# FilterControl_Schematic.net
KiCad netlist of a schematic drawn in Altium Designer
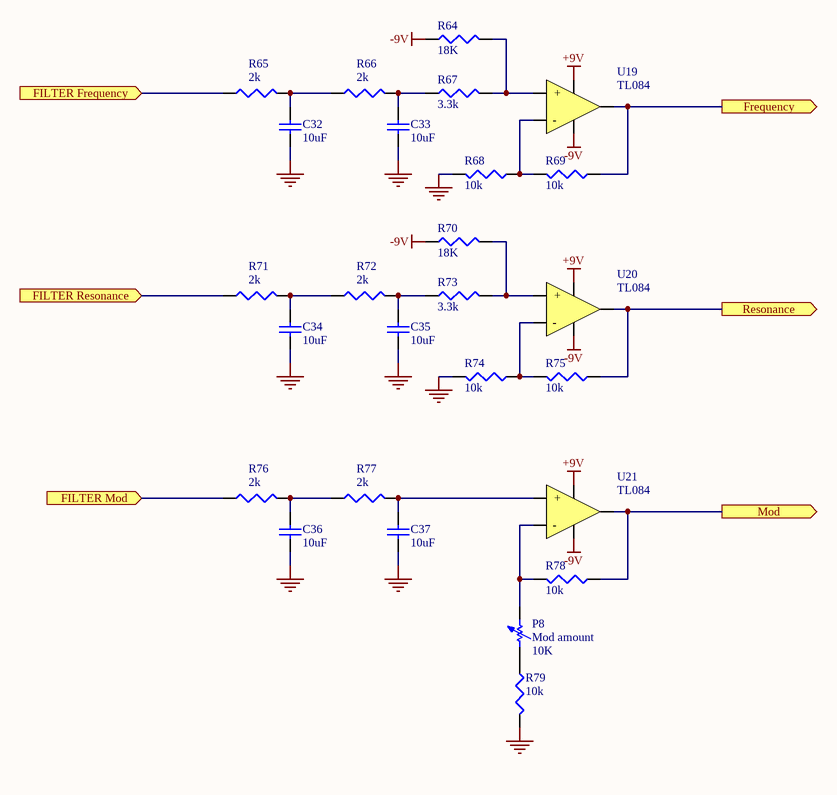
[diagram p0: FilterControl.Schematic.SchDoc]

(export (version "E")
  (design (tool "Eeschema 10.0.6"))
  (components
    (comp (ref "C32")
      (value "10uF")
      (footprint "CAPC1608N")
      (description "Capacitor (Semiconductor SIM Model)")
      (fields (field (name "PUBLISHER") "Altium Limited"))
      (libsource (lib "Miscellaneous Devices") (part "Cap Semi"))
    )
    (comp (ref "C33")
      (value "10uF")
      (footprint "CAPC1608N")
      (description "Capacitor (Semiconductor SIM Model)")
      (fields (field (name "PUBLISHER") "Altium Limited"))
      (libsource (lib "Miscellaneous Devices") (part "Cap Semi"))
    )
    (comp (ref "C34")
      (value "10uF")
      (footprint "CAPC1608N")
      (description "Capacitor (Semiconductor SIM Model)")
      (fields (field (name "PUBLISHER") "Altium Limited"))
      (libsource (lib "Miscellaneous Devices") (part "Cap Semi"))
    )
    (comp (ref "C35")
      (value "10uF")
      (footprint "CAPC1608N")
      (description "Capacitor (Semiconductor SIM Model)")
      (fields (field (name "PUBLISHER") "Altium Limited"))
      (libsource (lib "Miscellaneous Devices") (part "Cap Semi"))
    )
    (comp (ref "C36")
      (value "10uF")
      (footprint "CAPC1608N")
      (description "Capacitor (Semiconductor SIM Model)")
      (fields (field (name "PUBLISHER") "Altium Limited"))
      (libsource (lib "Miscellaneous Devices") (part "Cap Semi"))
    )
    (comp (ref "C37")
      (value "10uF")
      (footprint "CAPC1608N")
      (description "Capacitor (Semiconductor SIM Model)")
      (fields (field (name "PUBLISHER") "Altium Limited"))
      (libsource (lib "Miscellaneous Devices") (part "Cap Semi"))
    )
    (comp (ref "P8")
      (value "Mod amount")
      (footprint "AXIAL-0.7")
      (description "Variable Resistor")
      (fields (field (name "ALTIUM_VALUE") "10K") (field (name "PUBLISHER") "Altium Limited"))
      (libsource (lib "Miscellaneous Devices") (part "Res Adj1"))
    )
    (comp (ref "R64")
      (value "18K")
      (footprint "CAPC1608N")
      (description "Resistor")
      (fields (field (name "PUBLISHER") "Altium Limited"))
      (libsource (lib "Miscellaneous Devices") (part "Res3"))
    )
    (comp (ref "R65")
      (value "2k")
      (footprint "CAPC1608N")
      (description "Resistor")
      (fields (field (name "PUBLISHER") "Altium Limited"))
      (libsource (lib "Miscellaneous Devices") (part "Res3"))
    )
    (comp (ref "R66")
      (value "2k")
      (footprint "CAPC1608N")
      (description "Resistor")
      (fields (field (name "PUBLISHER") "Altium Limited"))
      (libsource (lib "Miscellaneous Devices") (part "Res3"))
    )
    (comp (ref "R67")
      (value "3.3k")
      (footprint "CAPC1608N")
      (description "Resistor")
      (fields (field (name "PUBLISHER") "Altium Limited"))
      (libsource (lib "Miscellaneous Devices") (part "Res3"))
    )
    (comp (ref "R68")
      (value "10k")
      (footprint "CAPC1608N")
      (description "Resistor")
      (fields (field (name "PUBLISHER") "Altium Limited"))
      (libsource (lib "Miscellaneous Devices") (part "Res3"))
    )
    (comp (ref "R69")
      (value "10k")
      (footprint "CAPC1608N")
      (description "Resistor")
      (fields (field (name "PUBLISHER") "Altium Limited"))
      (libsource (lib "Miscellaneous Devices") (part "Res3"))
    )
    (comp (ref "R70")
      (value "18K")
      (footprint "CAPC1608N")
      (description "Resistor")
      (fields (field (name "PUBLISHER") "Altium Limited"))
      (libsource (lib "Miscellaneous Devices") (part "Res3"))
    )
    (comp (ref "R71")
      (value "2k")
      (footprint "CAPC1608N")
      (description "Resistor")
      (fields (field (name "PUBLISHER") "Altium Limited"))
      (libsource (lib "Miscellaneous Devices") (part "Res3"))
    )
    (comp (ref "R72")
      (value "2k")
      (footprint "CAPC1608N")
      (description "Resistor")
      (fields (field (name "PUBLISHER") "Altium Limited"))
      (libsource (lib "Miscellaneous Devices") (part "Res3"))
    )
    (comp (ref "R73")
      (value "3.3k")
      (footprint "CAPC1608N")
      (description "Resistor")
      (fields (field (name "PUBLISHER") "Altium Limited"))
      (libsource (lib "Miscellaneous Devices") (part "Res3"))
    )
    (comp (ref "R74")
      (value "10k")
      (footprint "CAPC1608N")
      (description "Resistor")
      (fields (field (name "PUBLISHER") "Altium Limited"))
      (libsource (lib "Miscellaneous Devices") (part "Res3"))
    )
    (comp (ref "R75")
      (value "10k")
      (footprint "CAPC1608N")
      (description "Resistor")
      (fields (field (name "PUBLISHER") "Altium Limited"))
      (libsource (lib "Miscellaneous Devices") (part "Res3"))
    )
    (comp (ref "R76")
      (value "2k")
      (footprint "CAPC1608N")
      (description "Resistor")
      (fields (field (name "PUBLISHER") "Altium Limited"))
      (libsource (lib "Miscellaneous Devices") (part "Res3"))
    )
    (comp (ref "R77")
      (value "2k")
      (footprint "CAPC1608N")
      (description "Resistor")
      (fields (field (name "PUBLISHER") "Altium Limited"))
      (libsource (lib "Miscellaneous Devices") (part "Res3"))
    )
    (comp (ref "R78")
      (value "10k")
      (footprint "CAPC1608N")
      (description "Resistor")
      (fields (field (name "PUBLISHER") "Altium Limited"))
      (libsource (lib "Miscellaneous Devices") (part "Res3"))
    )
    (comp (ref "R79")
      (value "10k")
      (footprint "CAPC1608N")
      (description "Resistor")
      (fields (field (name "PUBLISHER") "Altium Limited"))
      (libsource (lib "Miscellaneous Devices") (part "Res3"))
    )
    (comp (ref "U19")
      (value "TL084")
      (footprint "TL084")
      (libsource (lib "SynthyTwo.Components") (part "TL084"))
    )
    (comp (ref "U20")
      (value "TL084")
      (footprint "TL084")
      (libsource (lib "SynthyTwo.Components") (part "TL084"))
    )
    (comp (ref "U21")
      (value "TL084")
      (footprint "TL084")
      (libsource (lib "SynthyTwo.Components") (part "TL084"))
    )
  )
  (nets
    (net (code "1") (name "+9V") (class "Default")
      (node (ref "U19") (pin "4") (pinfunction "VCC+_4") (pintype "passive"))
      (node (ref "U20") (pin "4") (pinfunction "VCC+_4") (pintype "passive"))
      (node (ref "U21") (pin "4") (pinfunction "VCC+_4") (pintype "passive"))
    )
    (net (code "2") (name "-9V") (class "Default")
      (node (ref "R64") (pin "1") (pinfunction "1_1") (pintype "passive"))
      (node (ref "R70") (pin "1") (pinfunction "1_1") (pintype "passive"))
      (node (ref "U19") (pin "11") (pinfunction "VCC-_11") (pintype "passive"))
      (node (ref "U20") (pin "11") (pinfunction "VCC-_11") (pintype "passive"))
      (node (ref "U21") (pin "11") (pinfunction "VCC-_11") (pintype "passive"))
    )
    (net (code "3") (name "/FILTER Frequency") (class "Default")
      (node (ref "R65") (pin "1") (pinfunction "1_1") (pintype "passive"))
    )
    (net (code "4") (name "/FILTER Mod") (class "Default")
      (node (ref "R76") (pin "1") (pinfunction "1_1") (pintype "passive"))
    )
    (net (code "5") (name "/FILTER Resonance") (class "Default")
      (node (ref "R71") (pin "1") (pinfunction "1_1") (pintype "passive"))
    )
    (net (code "6") (name "/Frequency") (class "Default")
      (node (ref "R69") (pin "1") (pinfunction "1_1") (pintype "passive"))
      (node (ref "U19") (pin "1") (pinfunction "OUT_1") (pintype "passive"))
    )
    (net (code "7") (name "/Mod") (class "Default")
      (node (ref "R78") (pin "1") (pinfunction "1_1") (pintype "passive"))
      (node (ref "U21") (pin "1") (pinfunction "OUT_1") (pintype "passive"))
    )
    (net (code "8") (name "/Resonance") (class "Default")
      (node (ref "R75") (pin "1") (pinfunction "1_1") (pintype "passive"))
      (node (ref "U20") (pin "1") (pinfunction "OUT_1") (pintype "passive"))
    )
    (net (code "9") (name "GND") (class "Default")
      (node (ref "C32") (pin "1") (pinfunction "1_1") (pintype "passive"))
      (node (ref "C33") (pin "1") (pinfunction "1_1") (pintype "passive"))
      (node (ref "C34") (pin "1") (pinfunction "1_1") (pintype "passive"))
      (node (ref "C35") (pin "1") (pinfunction "1_1") (pintype "passive"))
      (node (ref "C36") (pin "1") (pinfunction "1_1") (pintype "passive"))
      (node (ref "C37") (pin "1") (pinfunction "1_1") (pintype "passive"))
      (node (ref "R68") (pin "2") (pinfunction "2_2") (pintype "passive"))
      (node (ref "R74") (pin "2") (pinfunction "2_2") (pintype "passive"))
      (node (ref "R79") (pin "2") (pinfunction "2_2") (pintype "passive"))
    )
    (net (code "10") (name "Net-(C32-Pad2)") (class "Default")
      (node (ref "C32") (pin "2") (pinfunction "2_2") (pintype "passive"))
      (node (ref "R65") (pin "2") (pinfunction "2_2") (pintype "passive"))
      (node (ref "R66") (pin "1") (pinfunction "1_1") (pintype "passive"))
    )
    (net (code "11") (name "Net-(C33-Pad2)") (class "Default")
      (node (ref "C33") (pin "2") (pinfunction "2_2") (pintype "passive"))
      (node (ref "R66") (pin "2") (pinfunction "2_2") (pintype "passive"))
      (node (ref "R67") (pin "1") (pinfunction "1_1") (pintype "passive"))
    )
    (net (code "12") (name "Net-(C34-Pad2)") (class "Default")
      (node (ref "C34") (pin "2") (pinfunction "2_2") (pintype "passive"))
      (node (ref "R71") (pin "2") (pinfunction "2_2") (pintype "passive"))
      (node (ref "R72") (pin "1") (pinfunction "1_1") (pintype "passive"))
    )
    (net (code "13") (name "Net-(C35-Pad2)") (class "Default")
      (node (ref "C35") (pin "2") (pinfunction "2_2") (pintype "passive"))
      (node (ref "R72") (pin "2") (pinfunction "2_2") (pintype "passive"))
      (node (ref "R73") (pin "1") (pinfunction "1_1") (pintype "passive"))
    )
    (net (code "14") (name "Net-(C36-Pad2)") (class "Default")
      (node (ref "C36") (pin "2") (pinfunction "2_2") (pintype "passive"))
      (node (ref "R76") (pin "2") (pinfunction "2_2") (pintype "passive"))
      (node (ref "R77") (pin "1") (pinfunction "1_1") (pintype "passive"))
    )
    (net (code "15") (name "Net-(P8-Pad1)") (class "Default")
      (node (ref "P8") (pin "1") (pinfunction "1_1") (pintype "passive"))
      (node (ref "R79") (pin "1") (pinfunction "1_1") (pintype "passive"))
    )
    (net (code "16") (name "Net-(U19-+)") (class "Default")
      (node (ref "R64") (pin "2") (pinfunction "2_2") (pintype "passive"))
      (node (ref "R67") (pin "2") (pinfunction "2_2") (pintype "passive"))
      (node (ref "U19") (pin "2") (pinfunction "+_2") (pintype "passive"))
    )
    (net (code "17") (name "Net-(U19--)") (class "Default")
      (node (ref "R68") (pin "1") (pinfunction "1_1") (pintype "passive"))
      (node (ref "R69") (pin "2") (pinfunction "2_2") (pintype "passive"))
      (node (ref "U19") (pin "3") (pinfunction "-_3") (pintype "passive"))
    )
    (net (code "18") (name "Net-(U20-+)") (class "Default")
      (node (ref "R70") (pin "2") (pinfunction "2_2") (pintype "passive"))
      (node (ref "R73") (pin "2") (pinfunction "2_2") (pintype "passive"))
      (node (ref "U20") (pin "2") (pinfunction "+_2") (pintype "passive"))
    )
    (net (code "19") (name "Net-(U20--)") (class "Default")
      (node (ref "R74") (pin "1") (pinfunction "1_1") (pintype "passive"))
      (node (ref "R75") (pin "2") (pinfunction "2_2") (pintype "passive"))
      (node (ref "U20") (pin "3") (pinfunction "-_3") (pintype "passive"))
    )
    (net (code "20") (name "Net-(U21-+)") (class "Default")
      (node (ref "C37") (pin "2") (pinfunction "2_2") (pintype "passive"))
      (node (ref "R77") (pin "2") (pinfunction "2_2") (pintype "passive"))
      (node (ref "U21") (pin "2") (pinfunction "+_2") (pintype "passive"))
    )
    (net (code "21") (name "Net-(U21--)") (class "Default")
      (node (ref "P8") (pin "2") (pinfunction "2_2") (pintype "passive"))
      (node (ref "R78") (pin "2") (pinfunction "2_2") (pintype "passive"))
      (node (ref "U21") (pin "3") (pinfunction "-_3") (pintype "passive"))
    )
  )
)
